# pulseSensor.net
KiCad netlist of a schematic drawn in EAGLE
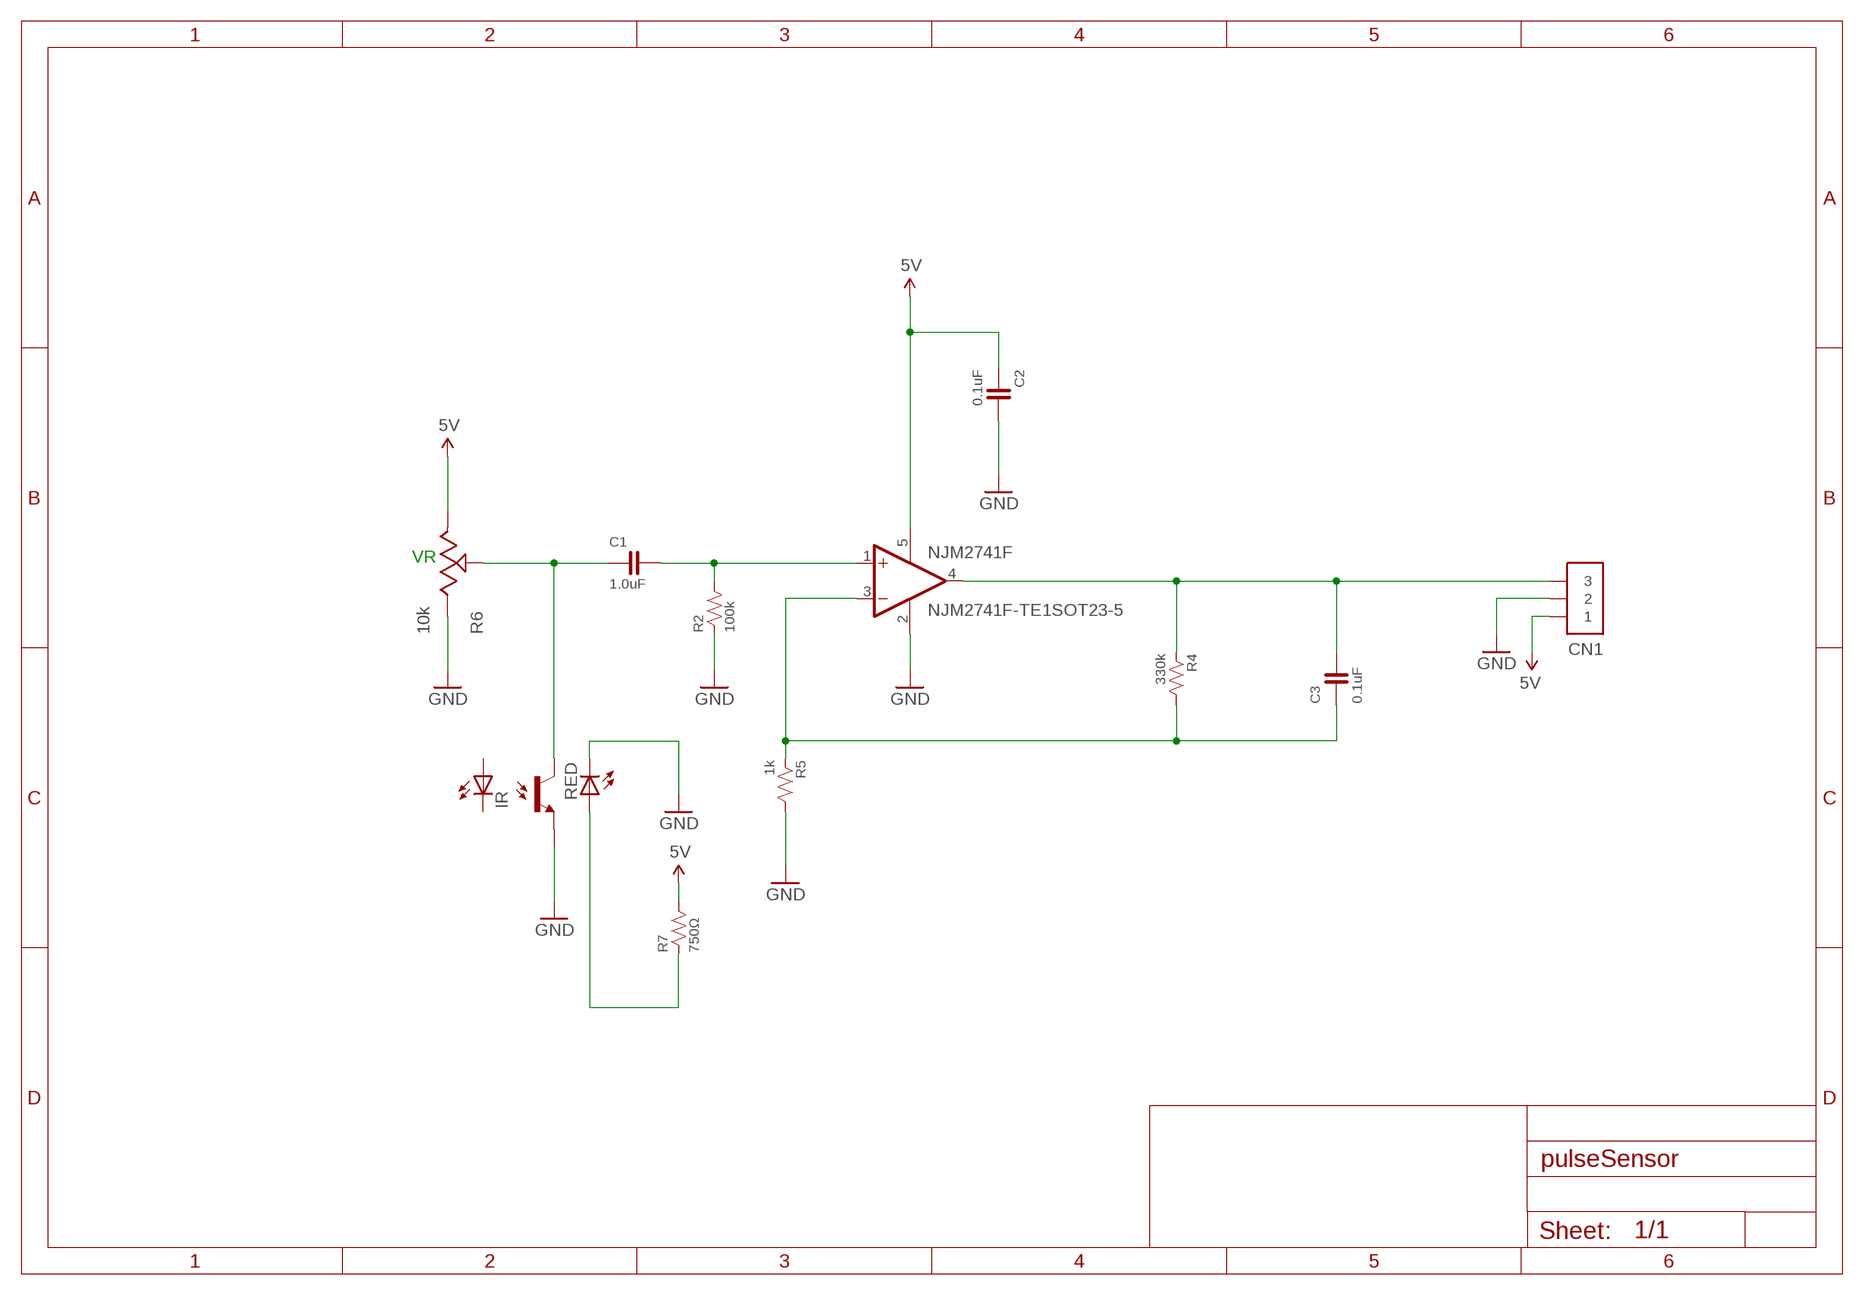
[diagram p0: schematic, sheet 1]

(export (version "E")
  (design (tool "Eeschema 10.0.6"))
  (components
    (comp (ref "C1")
      (value "1.0uF")
      (footprint "eagle-import:0603")
      (libsource (lib "eagle-import") (part "CAPACITOR-0603"))
    )
    (comp (ref "C2")
      (value "0.1uF")
      (footprint "eagle-import:0603")
      (libsource (lib "eagle-import") (part "CAPACITOR-0603"))
    )
    (comp (ref "C3")
      (value "0.1uF")
      (footprint "eagle-import:0603")
      (libsource (lib "eagle-import") (part "CAPACITOR-0603"))
    )
    (comp (ref "CN1")
      (value "PIN_HEADER_1X3")
      (footprint "eagle-import:PIN_1X3")
      (libsource (lib "eagle-import") (part "PIN_HEADER_1X3"))
    )
    (comp (ref "NJL1")
      (value "NJL5501R-TE1")
      (footprint "eagle-import:NJL5501R-PAC")
      (libsource (lib "eagle-import") (part "NJL5501R-TE1"))
    )
    (comp (ref "NJM2741F1")
      (value "NJM2741F-TE1SOT23-5")
      (footprint "eagle-import:NJL5501R-PAC")
      (libsource (lib "eagle-import") (part "NJM2741F-TE1SOT23-5"))
    )
    (comp (ref "R2")
      (value "100k")
      (footprint "eagle-import:0603")
      (libsource (lib "eagle-import") (part "RESISTOR-0603"))
    )
    (comp (ref "R4")
      (value "330k")
      (footprint "eagle-import:0603")
      (libsource (lib "eagle-import") (part "RESISTOR-0603"))
    )
    (comp (ref "R5")
      (value "1k")
      (footprint "eagle-import:0603")
      (libsource (lib "eagle-import") (part "RESISTOR-0603"))
    )
    (comp (ref "R6")
      (value "10k")
      (footprint "eagle-import:TC33X")
      (libsource (lib "eagle-import") (part "RESISTOR_VARIABLE-SMD"))
    )
    (comp (ref "R7")
      (value "750Ω")
      (footprint "eagle-import:0603")
      (libsource (lib "eagle-import") (part "RESISTOR-0603"))
    )
  )
  (nets
    (net (code "1") (name "5V") (class "Default")
      (node (ref "C2") (pin "1") (pinfunction "1_1") (pintype "passive"))
      (node (ref "CN1") (pin "1") (pinfunction "1_1") (pintype "bidirectional"))
      (node (ref "NJM2741F1") (pin "5") (pinfunction "V+_5") (pintype "power_in"))
      (node (ref "R6") (pin "1") (pinfunction "1_1") (pintype "passive"))
      (node (ref "R7") (pin "2") (pinfunction "2_2") (pintype "bidirectional"))
    )
    (net (code "2") (name "GND") (class "Default")
      (node (ref "C2") (pin "2") (pinfunction "2_2") (pintype "passive"))
      (node (ref "CN1") (pin "2") (pinfunction "2_2") (pintype "bidirectional"))
      (node (ref "NJL1") (pin "1") (pinfunction "1_1") (pintype "output"))
      (node (ref "NJM2741F1") (pin "2") (pinfunction "GND_2") (pintype "power_in"))
      (node (ref "R2") (pin "1") (pinfunction "1_1") (pintype "bidirectional"))
      (node (ref "R5") (pin "2") (pinfunction "2_2") (pintype "bidirectional"))
      (node (ref "R6") (pin "3") (pinfunction "3_3") (pintype "passive"))
    )
    (net (code "3") (name "Net-(C1-Pad1)") (class "Default")
      (node (ref "C1") (pin "1") (pinfunction "1_1") (pintype "passive"))
      (node (ref "NJL1") (pin "5") (pinfunction "5_5") (pintype "input"))
      (node (ref "R6") (pin "2") (pinfunction "2_2") (pintype "passive"))
    )
    (net (code "4") (name "Net-(NJL1-Pad6)") (class "Default")
      (node (ref "NJL1") (pin "6") (pinfunction "6_6") (pintype "input"))
      (node (ref "R7") (pin "1") (pinfunction "1_1") (pintype "bidirectional"))
    )
    (net (code "5") (name "Net-(NJM2741F1-+IN)") (class "Default")
      (node (ref "C1") (pin "2") (pinfunction "2_2") (pintype "passive"))
      (node (ref "NJM2741F1") (pin "1") (pinfunction "+IN_1") (pintype "input"))
      (node (ref "R2") (pin "2") (pinfunction "2_2") (pintype "bidirectional"))
    )
    (net (code "6") (name "Net-(NJM2741F1--IN)") (class "Default")
      (node (ref "C3") (pin "1") (pinfunction "1_1") (pintype "passive"))
      (node (ref "NJM2741F1") (pin "3") (pinfunction "-IN_3") (pintype "input"))
      (node (ref "R4") (pin "2") (pinfunction "2_2") (pintype "bidirectional"))
      (node (ref "R5") (pin "1") (pinfunction "1_1") (pintype "bidirectional"))
    )
    (net (code "7") (name "Net-(NJM2741F1-OUT)") (class "Default")
      (node (ref "C3") (pin "2") (pinfunction "2_2") (pintype "passive"))
      (node (ref "CN1") (pin "3") (pinfunction "3_3") (pintype "bidirectional"))
      (node (ref "NJM2741F1") (pin "4") (pinfunction "OUT_4") (pintype "output"))
      (node (ref "R4") (pin "1") (pinfunction "1_1") (pintype "bidirectional"))
    )
    (net (code "8") (name "unconnected-(NJL1-Pad2)") (class "Default")
      (node (ref "NJL1") (pin "2") (pinfunction "2_2") (pintype "output"))
    )
    (net (code "9") (name "unconnected-(NJL1-Pad3)") (class "Default")
      (node (ref "NJL1") (pin "3") (pinfunction "3_3") (pintype "input"))
    )
    (net (code "10") (name "unconnected-(NJL1-Pad4)") (class "Default")
      (node (ref "NJL1") (pin "4") (pinfunction "4_4") (pintype "output"))
    )
  )
)
